# glove-snap.net
KiCad netlist of a schematic drawn in EAGLE
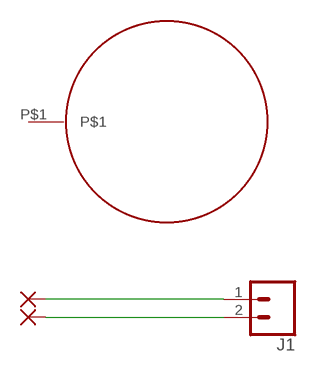
[diagram p0: schematic, sheet 1]

(export (version "E")
  (design (tool "Eeschema 10.0.6"))
  (components
    (comp (ref "J1")
      (value "CONN_02LOCK_LONGPADS")
      (footprint "eagle-import:1X02_LOCK_LONGPADS")
      (libsource (lib "eagle-import") (part "CONN_02LOCK_LONGPADS"))
    )
    (comp (ref "PAD1")
      (value "WIREPADSMD2,54-5,08")
      (footprint "eagle-import:SMD2,54-5,08")
      (libsource (lib "eagle-import") (part "WIREPADSMD2,54-5,08"))
    )
    (comp (ref "PAD2")
      (value "WIREPADSMD2,54-5,08")
      (footprint "eagle-import:SMD2,54-5,08")
      (libsource (lib "eagle-import") (part "WIREPADSMD2,54-5,08"))
    )
    (comp (ref "U$1")
      (value "SNAP")
      (footprint "eagle-import:SNAP")
      (libsource (lib "eagle-import") (part "SNAP"))
    )
  )
  (nets
    (net (code "1") (name "Net-(PAD1-P)") (class "Default")
      (node (ref "J1") (pin "1") (pinfunction "1_1") (pintype "passive"))
      (node (ref "PAD1") (pin "1") (pinfunction "P_1") (pintype "passive"))
    )
    (net (code "2") (name "Net-(PAD2-P)") (class "Default")
      (node (ref "J1") (pin "2") (pinfunction "2_2") (pintype "passive"))
      (node (ref "PAD2") (pin "1") (pinfunction "P_1") (pintype "passive"))
    )
    (net (code "3") (name "unconnected-(U$1-PadP$1)") (class "Default")
      (node (ref "U$1") (pin "P$1") (pinfunction "P$1_P$1") (pintype "bidirectional"))
    )
  )
)
